# pmod-apa102.net
KiCad netlist of a schematic drawn in EAGLE
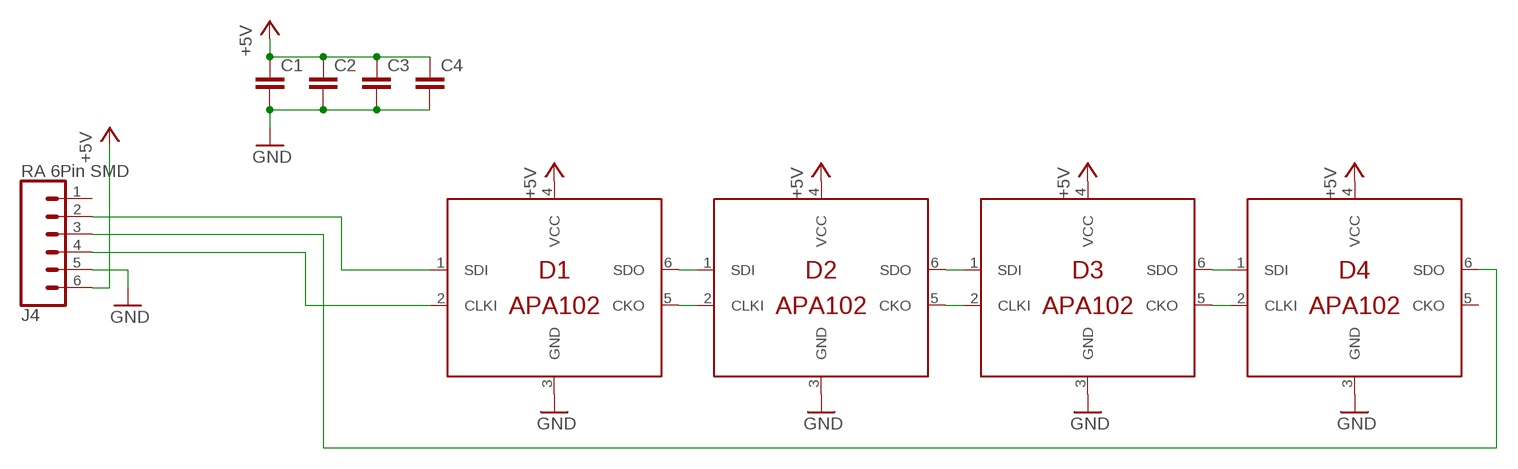
[diagram p0: schematic, sheet 1]

(export (version "E")
  (design (tool "Eeschema 10.0.6"))
  (components
    (comp (ref "C1")
      (value "C-EUC0805K")
      (footprint "eagle-import:C0805K")
      (libsource (lib "eagle-import") (part "C-EUC0805K"))
    )
    (comp (ref "C2")
      (value "C-EUC0805K")
      (footprint "eagle-import:C0805K")
      (libsource (lib "eagle-import") (part "C-EUC0805K"))
    )
    (comp (ref "C3")
      (value "C-EUC0805K")
      (footprint "eagle-import:C0805K")
      (libsource (lib "eagle-import") (part "C-EUC0805K"))
    )
    (comp (ref "C4")
      (value "C-EUC0805K")
      (footprint "eagle-import:C0805K")
      (libsource (lib "eagle-import") (part "C-EUC0805K"))
    )
    (comp (ref "D1")
      (value "APA102")
      (footprint "eagle-import:RGBLED5050")
      (libsource (lib "eagle-import") (part "APA102"))
    )
    (comp (ref "D2")
      (value "APA102")
      (footprint "eagle-import:RGBLED5050")
      (libsource (lib "eagle-import") (part "APA102"))
    )
    (comp (ref "D3")
      (value "APA102")
      (footprint "eagle-import:RGBLED5050")
      (libsource (lib "eagle-import") (part "APA102"))
    )
    (comp (ref "D4")
      (value "APA102")
      (footprint "eagle-import:RGBLED5050")
      (libsource (lib "eagle-import") (part "APA102"))
    )
    (comp (ref "J4")
      (value "RA 6Pin SMD")
      (footprint "eagle-import:1X06-SMD_RA_MALE")
      (libsource (lib "eagle-import") (part "CONN_06SMD"))
    )
  )
  (nets
    (net (code "1") (name "+5V") (class "Default")
      (node (ref "C1") (pin "1") (pinfunction "1_1") (pintype "passive"))
      (node (ref "C2") (pin "1") (pinfunction "1_1") (pintype "passive"))
      (node (ref "C3") (pin "1") (pinfunction "1_1") (pintype "passive"))
      (node (ref "C4") (pin "1") (pinfunction "1_1") (pintype "passive"))
      (node (ref "D1") (pin "4") (pinfunction "VCC_4") (pintype "bidirectional"))
      (node (ref "D2") (pin "4") (pinfunction "VCC_4") (pintype "bidirectional"))
      (node (ref "D3") (pin "4") (pinfunction "VCC_4") (pintype "bidirectional"))
      (node (ref "D4") (pin "4") (pinfunction "VCC_4") (pintype "bidirectional"))
      (node (ref "J4") (pin "6") (pinfunction "6_6") (pintype "passive"))
    )
    (net (code "2") (name "GND") (class "Default")
      (node (ref "C1") (pin "2") (pinfunction "2_2") (pintype "passive"))
      (node (ref "C2") (pin "2") (pinfunction "2_2") (pintype "passive"))
      (node (ref "C3") (pin "2") (pinfunction "2_2") (pintype "passive"))
      (node (ref "C4") (pin "2") (pinfunction "2_2") (pintype "passive"))
      (node (ref "D1") (pin "3") (pinfunction "GND_3") (pintype "bidirectional"))
      (node (ref "D2") (pin "3") (pinfunction "GND_3") (pintype "bidirectional"))
      (node (ref "D3") (pin "3") (pinfunction "GND_3") (pintype "bidirectional"))
      (node (ref "D4") (pin "3") (pinfunction "GND_3") (pintype "bidirectional"))
      (node (ref "J4") (pin "5") (pinfunction "5_5") (pintype "passive"))
    )
    (net (code "3") (name "Net-(D1-CKO)") (class "Default")
      (node (ref "D1") (pin "5") (pinfunction "CKO_5") (pintype "output"))
      (node (ref "D2") (pin "2") (pinfunction "CLKI_2") (pintype "input"))
    )
    (net (code "4") (name "Net-(D1-CLKI)") (class "Default")
      (node (ref "D1") (pin "2") (pinfunction "CLKI_2") (pintype "input"))
      (node (ref "J4") (pin "4") (pinfunction "4_4") (pintype "passive"))
    )
    (net (code "5") (name "Net-(D1-SDI)") (class "Default")
      (node (ref "D1") (pin "1") (pinfunction "SDI_1") (pintype "input"))
      (node (ref "J4") (pin "2") (pinfunction "2_2") (pintype "passive"))
    )
    (net (code "6") (name "Net-(D1-SDO)") (class "Default")
      (node (ref "D1") (pin "6") (pinfunction "SDO_6") (pintype "output"))
      (node (ref "D2") (pin "1") (pinfunction "SDI_1") (pintype "input"))
    )
    (net (code "7") (name "Net-(D2-CKO)") (class "Default")
      (node (ref "D2") (pin "5") (pinfunction "CKO_5") (pintype "output"))
      (node (ref "D3") (pin "2") (pinfunction "CLKI_2") (pintype "input"))
    )
    (net (code "8") (name "Net-(D2-SDO)") (class "Default")
      (node (ref "D2") (pin "6") (pinfunction "SDO_6") (pintype "output"))
      (node (ref "D3") (pin "1") (pinfunction "SDI_1") (pintype "input"))
    )
    (net (code "9") (name "Net-(D3-CKO)") (class "Default")
      (node (ref "D3") (pin "5") (pinfunction "CKO_5") (pintype "output"))
      (node (ref "D4") (pin "2") (pinfunction "CLKI_2") (pintype "input"))
    )
    (net (code "10") (name "Net-(D3-SDO)") (class "Default")
      (node (ref "D3") (pin "6") (pinfunction "SDO_6") (pintype "output"))
      (node (ref "D4") (pin "1") (pinfunction "SDI_1") (pintype "input"))
    )
    (net (code "11") (name "Net-(D4-SDO)") (class "Default")
      (node (ref "D4") (pin "6") (pinfunction "SDO_6") (pintype "output"))
      (node (ref "J4") (pin "3") (pinfunction "3_3") (pintype "passive"))
    )
    (net (code "12") (name "unconnected-(D4-CKO-Pad5)") (class "Default")
      (node (ref "D4") (pin "5") (pinfunction "CKO_5") (pintype "output"))
    )
    (net (code "13") (name "unconnected-(J4-Pad1)") (class "Default")
      (node (ref "J4") (pin "1") (pinfunction "1_1") (pintype "passive"))
    )
  )
)
